# 8RelaySwitch.net
KiCad netlist of a schematic drawn in EAGLE
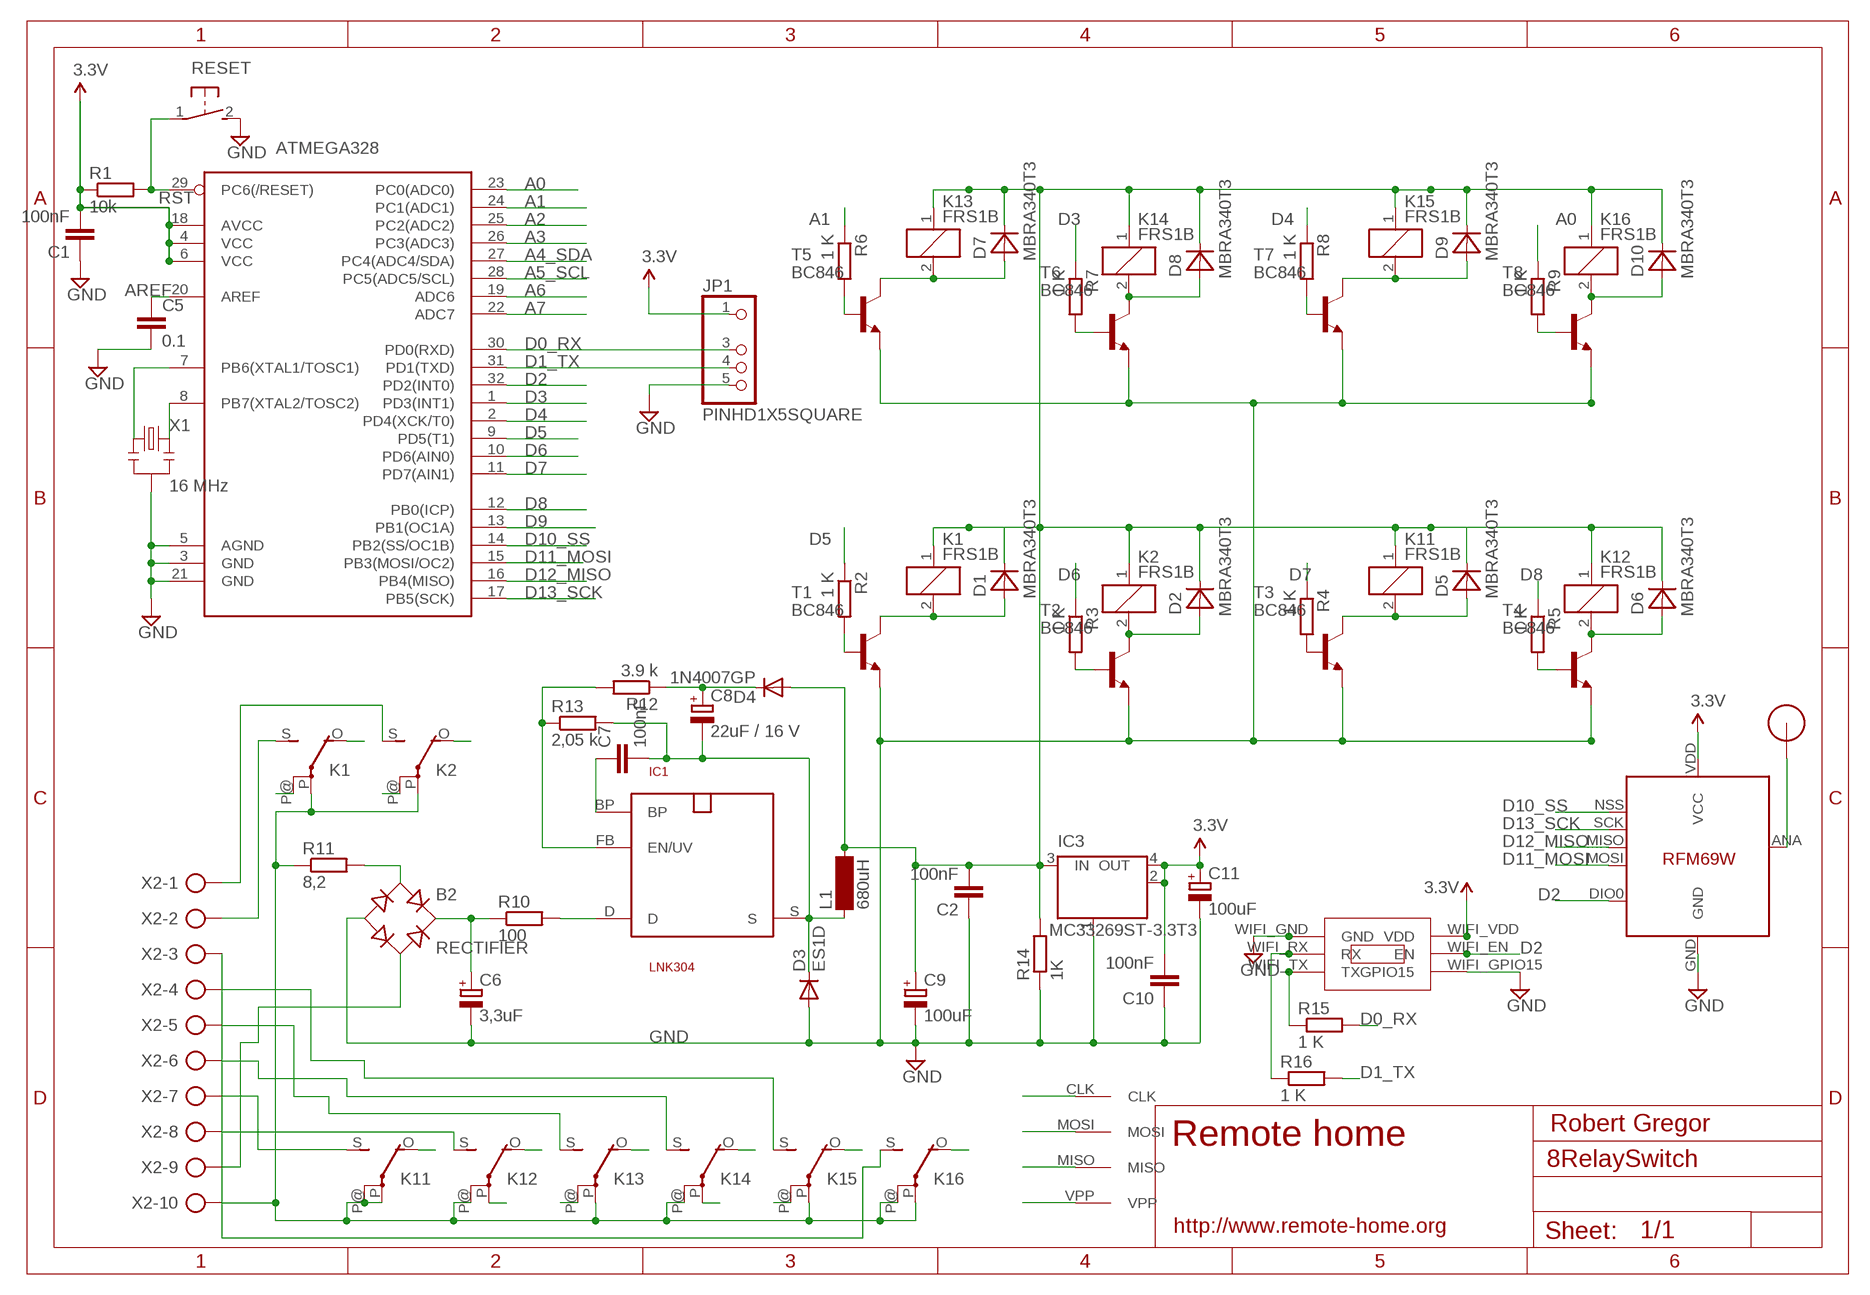
[diagram p0: schematic, sheet 1]

(export (version "E")
  (design (tool "Eeschema 10.0.6"))
  (components
    (comp (ref "ATMEGA328")
      (value "ATMega-328")
      (footprint "eagle-import:TQFP32-08")
      (libsource (lib "eagle-import") (part "ATMEGA168/328TQFP32"))
    )
    (comp (ref "B2")
      (value "RECTIFIER")
      (footprint "eagle-import:TO-269AA")
      (libsource (lib "eagle-import") (part "RECTIFIER-S40"))
    )
    (comp (ref "C1")
      (value "100nF")
      (footprint "eagle-import:C2012")
      (libsource (lib "eagle-import") (part "C-EUC2012"))
    )
    (comp (ref "C2")
      (value "100nF")
      (footprint "eagle-import:C2012")
      (libsource (lib "eagle-import") (part "C-EUC2012"))
    )
    (comp (ref "C5")
      (value "0.1")
      (footprint "eagle-import:C2012")
      (libsource (lib "eagle-import") (part "C-EUC2012"))
    )
    (comp (ref "C6")
      (value "3,3uF")
      (footprint "eagle-import:E5-10,5")
      (libsource (lib "eagle-import") (part "CPOL-EUE5-10.5"))
    )
    (comp (ref "C7")
      (value "100nF")
      (footprint "eagle-import:C2012")
      (libsource (lib "eagle-import") (part "C-EUC2012"))
    )
    (comp (ref "C8")
      (value "22uF / 16 V")
      (footprint "eagle-import:SMC_C")
      (libsource (lib "eagle-import") (part "CPOL-EUSMCC"))
    )
    (comp (ref "C9")
      (value "100uF")
      (footprint "eagle-import:SMC_B")
      (libsource (lib "eagle-import") (part "CPOL-EUSMCB"))
    )
    (comp (ref "C10")
      (value "100nF")
      (footprint "eagle-import:C2012")
      (libsource (lib "eagle-import") (part "C-EUC2012"))
    )
    (comp (ref "C11")
      (value "100uF")
      (footprint "eagle-import:SMC_B")
      (libsource (lib "eagle-import") (part "CPOL-EUSMCB"))
    )
    (comp (ref "D1")
      (value "MBRA340T3")
      (footprint "eagle-import:SMA")
      (libsource (lib "eagle-import") (part "MBRA340T3"))
    )
    (comp (ref "D2")
      (value "MBRA340T3")
      (footprint "eagle-import:SMA")
      (libsource (lib "eagle-import") (part "MBRA340T3"))
    )
    (comp (ref "D3")
      (value "ES1D")
      (footprint "eagle-import:DO214AC")
      (libsource (lib "eagle-import") (part "DIODE-DO214AC"))
    )
    (comp (ref "D4")
      (value "1N4007GP")
      (footprint "eagle-import:DO214AA")
      (libsource (lib "eagle-import") (part "DIODE-DO214AA"))
    )
    (comp (ref "D5")
      (value "MBRA340T3")
      (footprint "eagle-import:SMA")
      (libsource (lib "eagle-import") (part "MBRA340T3"))
    )
    (comp (ref "D6")
      (value "MBRA340T3")
      (footprint "eagle-import:SMA")
      (libsource (lib "eagle-import") (part "MBRA340T3"))
    )
    (comp (ref "D7")
      (value "MBRA340T3")
      (footprint "eagle-import:SMA")
      (libsource (lib "eagle-import") (part "MBRA340T3"))
    )
    (comp (ref "D8")
      (value "MBRA340T3")
      (footprint "eagle-import:SMA")
      (libsource (lib "eagle-import") (part "MBRA340T3"))
    )
    (comp (ref "D9")
      (value "MBRA340T3")
      (footprint "eagle-import:SMA")
      (libsource (lib "eagle-import") (part "MBRA340T3"))
    )
    (comp (ref "D10")
      (value "MBRA340T3")
      (footprint "eagle-import:SMA")
      (libsource (lib "eagle-import") (part "MBRA340T3"))
    )
    (comp (ref "IC1")
      (value "LNK304")
      (footprint "eagle-import:SO-8C")
      (libsource (lib "eagle-import") (part "SO-8C"))
    )
    (comp (ref "IC3")
      (value "MC33269ST-3.3T3")
      (footprint "eagle-import:SOT223")
      (libsource (lib "eagle-import") (part "MC33269ST-3.3T3"))
    )
    (comp (ref "JP1")
      (value "PINHD1X5SQUARE")
      (footprint "eagle-import:PINHD1X05-SQUARE")
      (libsource (lib "eagle-import") (part "PINHD1X5SQUARE"))
    )
    (comp (ref "K1")
      (value "FRS1B")
      (footprint "eagle-import:FRS1B")
      (libsource (lib "eagle-import") (part "FRS1B"))
    )
    (comp (ref "K2")
      (value "FRS1B")
      (footprint "eagle-import:FRS1B")
      (libsource (lib "eagle-import") (part "FRS1B"))
    )
    (comp (ref "K11")
      (value "FRS1B")
      (footprint "eagle-import:FRS1B")
      (libsource (lib "eagle-import") (part "FRS1B"))
    )
    (comp (ref "K12")
      (value "FRS1B")
      (footprint "eagle-import:FRS1B")
      (libsource (lib "eagle-import") (part "FRS1B"))
    )
    (comp (ref "K13")
      (value "FRS1B")
      (footprint "eagle-import:FRS1B")
      (libsource (lib "eagle-import") (part "FRS1B"))
    )
    (comp (ref "K14")
      (value "FRS1B")
      (footprint "eagle-import:FRS1B")
      (libsource (lib "eagle-import") (part "FRS1B"))
    )
    (comp (ref "K15")
      (value "FRS1B")
      (footprint "eagle-import:FRS1B")
      (libsource (lib "eagle-import") (part "FRS1B"))
    )
    (comp (ref "K16")
      (value "FRS1B")
      (footprint "eagle-import:FRS1B")
      (libsource (lib "eagle-import") (part "FRS1B"))
    )
    (comp (ref "L1")
      (value "680uH")
      (footprint "eagle-import:SD8")
      (libsource (lib "eagle-import") (part "SD8"))
    )
    (comp (ref "R1")
      (value "10k")
      (footprint "eagle-import:R2012")
      (libsource (lib "eagle-import") (part "R-EU_R2012"))
    )
    (comp (ref "R2")
      (value "1 K")
      (footprint "eagle-import:M2012")
      (libsource (lib "eagle-import") (part "R-EU_M2012"))
    )
    (comp (ref "R3")
      (value "1 K")
      (footprint "eagle-import:M2012")
      (libsource (lib "eagle-import") (part "R-EU_M2012"))
    )
    (comp (ref "R4")
      (value "1 K")
      (footprint "eagle-import:M2012")
      (libsource (lib "eagle-import") (part "R-EU_M2012"))
    )
    (comp (ref "R5")
      (value "1 K")
      (footprint "eagle-import:M2012")
      (libsource (lib "eagle-import") (part "R-EU_M2012"))
    )
    (comp (ref "R6")
      (value "1 K")
      (footprint "eagle-import:M2012")
      (libsource (lib "eagle-import") (part "R-EU_M2012"))
    )
    (comp (ref "R7")
      (value "1 K")
      (footprint "eagle-import:M2012")
      (libsource (lib "eagle-import") (part "R-EU_M2012"))
    )
    (comp (ref "R8")
      (value "1 K")
      (footprint "eagle-import:M2012")
      (libsource (lib "eagle-import") (part "R-EU_M2012"))
    )
    (comp (ref "R9")
      (value "1 K")
      (footprint "eagle-import:M2012")
      (libsource (lib "eagle-import") (part "R-EU_M2012"))
    )
    (comp (ref "R10")
      (value "100")
      (footprint "eagle-import:R2512W")
      (libsource (lib "eagle-import") (part "R-EU_R2512W"))
    )
    (comp (ref "R11")
      (value "8,2")
      (footprint "eagle-import:0411_12")
      (libsource (lib "eagle-import") (part "R-EU_0411/12"))
    )
    (comp (ref "R12")
      (value "3.9 k")
      (footprint "eagle-import:M2012")
      (libsource (lib "eagle-import") (part "R-EU_M2012"))
    )
    (comp (ref "R13")
      (value "2,05 k")
      (footprint "eagle-import:M2012")
      (libsource (lib "eagle-import") (part "R-EU_M2012"))
    )
    (comp (ref "R14")
      (value "1K")
      (footprint "eagle-import:M2012")
      (libsource (lib "eagle-import") (part "R-EU_M2012"))
    )
    (comp (ref "R15")
      (value "1 K")
      (footprint "eagle-import:M2012")
      (libsource (lib "eagle-import") (part "R-EU_M2012"))
    )
    (comp (ref "R16")
      (value "1 K")
      (footprint "eagle-import:M2012")
      (libsource (lib "eagle-import") (part "R-EU_M2012"))
    )
    (comp (ref "RESET")
      (value "DTSM-3")
      (footprint "eagle-import:DTSM-3")
      (libsource (lib "eagle-import") (part "DTSM-3"))
    )
    (comp (ref "T1")
      (value "BC846")
      (footprint "eagle-import:SOT23")
      (libsource (lib "eagle-import") (part "BC846"))
    )
    (comp (ref "T2")
      (value "BC846")
      (footprint "eagle-import:SOT23")
      (libsource (lib "eagle-import") (part "BC846"))
    )
    (comp (ref "T3")
      (value "BC846")
      (footprint "eagle-import:SOT23")
      (libsource (lib "eagle-import") (part "BC846"))
    )
    (comp (ref "T4")
      (value "BC846")
      (footprint "eagle-import:SOT23")
      (libsource (lib "eagle-import") (part "BC846"))
    )
    (comp (ref "T5")
      (value "BC846")
      (footprint "eagle-import:SOT23")
      (libsource (lib "eagle-import") (part "BC846"))
    )
    (comp (ref "T6")
      (value "BC846")
      (footprint "eagle-import:SOT23")
      (libsource (lib "eagle-import") (part "BC846"))
    )
    (comp (ref "T7")
      (value "BC846")
      (footprint "eagle-import:SOT23")
      (libsource (lib "eagle-import") (part "BC846"))
    )
    (comp (ref "T8")
      (value "BC846")
      (footprint "eagle-import:SOT23")
      (libsource (lib "eagle-import") (part "BC846"))
    )
    (comp (ref "U$1")
      (value "RFM12B_ANTENNA")
      (footprint "eagle-import:RFM12B-ANTENNA")
      (libsource (lib "eagle-import") (part "RFM12B_ANTENNA"))
    )
    (comp (ref "U$2")
      (value "AVRHEADERDIP")
      (footprint "eagle-import:AVRHEADER")
      (libsource (lib "eagle-import") (part "AVRHEADERDIP"))
    )
    (comp (ref "U$3")
      (value "ESP03")
      (footprint "eagle-import:ESP03")
      (libsource (lib "eagle-import") (part "ESP03"))
    )
    (comp (ref "U$5")
      (value "RFM69")
      (footprint "eagle-import:RFM69W-MINPADS")
      (libsource (lib "eagle-import") (part "RFM69"))
    )
    (comp (ref "X1")
      (value "16 MHz")
      (footprint "eagle-import:RESONATOR-SMD")
      (libsource (lib "eagle-import") (part "RESONATORSMD"))
    )
    (comp (ref "X2")
      (value "AK500/10")
      (footprint "eagle-import:AK500_10")
      (libsource (lib "eagle-import") (part "AK500/10"))
    )
  )
  (nets
    (net (code "1") (name "/A0") (class "Default")
      (node (ref "ATMEGA328") (pin "23") (pinfunction "PC0(ADC0)_23") (pintype "bidirectional"))
      (node (ref "R9") (pin "1") (pinfunction "1_1") (pintype "passive"))
    )
    (net (code "2") (name "/A1") (class "Default")
      (node (ref "ATMEGA328") (pin "24") (pinfunction "PC1(ADC1)_24") (pintype "bidirectional"))
      (node (ref "R6") (pin "1") (pinfunction "1_1") (pintype "passive"))
    )
    (net (code "3") (name "/A2") (class "Default")
      (node (ref "ATMEGA328") (pin "25") (pinfunction "PC2(ADC2)_25") (pintype "bidirectional"))
    )
    (net (code "4") (name "/A3") (class "Default")
      (node (ref "ATMEGA328") (pin "26") (pinfunction "PC3(ADC3)_26") (pintype "bidirectional"))
    )
    (net (code "5") (name "/A4_SDA") (class "Default")
      (node (ref "ATMEGA328") (pin "27") (pinfunction "PC4(ADC4/SDA)_27") (pintype "bidirectional"))
    )
    (net (code "6") (name "/A5_SCL") (class "Default")
      (node (ref "ATMEGA328") (pin "28") (pinfunction "PC5(ADC5/SCL)_28") (pintype "bidirectional"))
    )
    (net (code "7") (name "/A6") (class "Default")
      (node (ref "ATMEGA328") (pin "19") (pinfunction "ADC6_19") (pintype "bidirectional"))
    )
    (net (code "8") (name "/A7") (class "Default")
      (node (ref "ATMEGA328") (pin "22") (pinfunction "ADC7_22") (pintype "bidirectional"))
    )
    (net (code "9") (name "/AREF") (class "Default")
      (node (ref "ATMEGA328") (pin "20") (pinfunction "AREF_20") (pintype "bidirectional"))
      (node (ref "C5") (pin "1") (pinfunction "1_1") (pintype "passive"))
    )
    (net (code "10") (name "/D0_RX") (class "Default")
      (node (ref "ATMEGA328") (pin "30") (pinfunction "PD0(RXD)_30") (pintype "bidirectional"))
      (node (ref "JP1") (pin "3") (pinfunction "3_3") (pintype "passive"))
      (node (ref "R15") (pin "2") (pinfunction "2_2") (pintype "passive"))
    )
    (net (code "11") (name "/D1_TX") (class "Default")
      (node (ref "ATMEGA328") (pin "31") (pinfunction "PD1(TXD)_31") (pintype "bidirectional"))
      (node (ref "JP1") (pin "4") (pinfunction "4_4") (pintype "passive"))
      (node (ref "R16") (pin "2") (pinfunction "2_2") (pintype "passive"))
    )
    (net (code "12") (name "/D2") (class "Default")
      (node (ref "ATMEGA328") (pin "32") (pinfunction "PD2(INT0)_32") (pintype "bidirectional"))
      (node (ref "U$3") (pin "WIFI_EN") (pinfunction "EN_WIFI_EN") (pintype "input"))
      (node (ref "U$5") (pin "DIO0") (pinfunction "DIO0_DIO0") (pintype "open_collector"))
    )
    (net (code "13") (name "/D3") (class "Default")
      (node (ref "ATMEGA328") (pin "1") (pinfunction "PD3(INT1)_1") (pintype "bidirectional"))
      (node (ref "R7") (pin "1") (pinfunction "1_1") (pintype "passive"))
    )
    (net (code "14") (name "/D4") (class "Default")
      (node (ref "ATMEGA328") (pin "2") (pinfunction "PD4(XCK/T0)_2") (pintype "bidirectional"))
      (node (ref "R8") (pin "1") (pinfunction "1_1") (pintype "passive"))
    )
    (net (code "15") (name "/D5") (class "Default")
      (node (ref "ATMEGA328") (pin "9") (pinfunction "PD5(T1)_9") (pintype "bidirectional"))
      (node (ref "R2") (pin "1") (pinfunction "1_1") (pintype "passive"))
    )
    (net (code "16") (name "/D6") (class "Default")
      (node (ref "ATMEGA328") (pin "10") (pinfunction "PD6(AIN0)_10") (pintype "bidirectional"))
      (node (ref "R3") (pin "1") (pinfunction "1_1") (pintype "passive"))
    )
    (net (code "17") (name "/D7") (class "Default")
      (node (ref "ATMEGA328") (pin "11") (pinfunction "PD7(AIN1)_11") (pintype "bidirectional"))
      (node (ref "R4") (pin "1") (pinfunction "1_1") (pintype "passive"))
    )
    (net (code "18") (name "/D8") (class "Default")
      (node (ref "ATMEGA328") (pin "12") (pinfunction "PB0(ICP)_12") (pintype "bidirectional"))
      (node (ref "R5") (pin "1") (pinfunction "1_1") (pintype "passive"))
    )
    (net (code "19") (name "/D9") (class "Default")
      (node (ref "ATMEGA328") (pin "13") (pinfunction "PB1(OC1A)_13") (pintype "bidirectional"))
    )
    (net (code "20") (name "/D10_SS") (class "Default")
      (node (ref "ATMEGA328") (pin "14") (pinfunction "PB2(SS/OC1B)_14") (pintype "bidirectional"))
      (node (ref "U$5") (pin "NSS") (pinfunction "SEL_NSS") (pintype "input"))
    )
    (net (code "21") (name "/D11_MOSI") (class "Default")
      (node (ref "ATMEGA328") (pin "15") (pinfunction "PB3(MOSI/OC2)_15") (pintype "bidirectional"))
      (node (ref "U$2") (pin "MOSI") (pinfunction "MOSI_MOSI") (pintype "bidirectional"))
      (node (ref "U$5") (pin "MOSI") (pinfunction "MOSI_MOSI") (pintype "output"))
    )
    (net (code "22") (name "/D12_MISO") (class "Default")
      (node (ref "ATMEGA328") (pin "16") (pinfunction "PB4(MISO)_16") (pintype "bidirectional"))
      (node (ref "U$2") (pin "MISO") (pinfunction "MISO_MISO") (pintype "bidirectional"))
      (node (ref "U$5") (pin "MISO") (pinfunction "MISO_MISO") (pintype "input"))
    )
    (net (code "23") (name "/D13_SCK") (class "Default")
      (node (ref "ATMEGA328") (pin "17") (pinfunction "PB5(SCK)_17") (pintype "bidirectional"))
      (node (ref "U$2") (pin "CLK") (pinfunction "CLK_CLK") (pintype "bidirectional"))
      (node (ref "U$5") (pin "SCK") (pinfunction "SCK_SCK") (pintype "input"))
    )
    (net (code "24") (name "/RST") (class "Default")
      (node (ref "ATMEGA328") (pin "29") (pinfunction "PC6(/RESET)_29") (pintype "bidirectional"))
      (node (ref "R1") (pin "2") (pinfunction "2_2") (pintype "passive"))
      (node (ref "RESET") (pin "1") (pinfunction "1_1") (pintype "passive"))
      (node (ref "U$2") (pin "VPP") (pinfunction "VPP_VPP") (pintype "bidirectional"))
    )
    (net (code "25") (name "3.3V") (class "Default")
      (node (ref "ATMEGA328") (pin "18") (pinfunction "AVCC_18") (pintype "bidirectional"))
      (node (ref "ATMEGA328") (pin "4") (pinfunction "VCC_4") (pintype "bidirectional"))
      (node (ref "ATMEGA328") (pin "6") (pinfunction "VCC_6") (pintype "bidirectional"))
      (node (ref "C1") (pin "2") (pinfunction "2_2") (pintype "passive"))
      (node (ref "C10") (pin "2") (pinfunction "2_2") (pintype "passive"))
      (node (ref "C11") (pin "+") (pinfunction "+_+") (pintype "passive"))
      (node (ref "IC3") (pin "2") (pinfunction "OUT_2") (pintype "passive"))
      (node (ref "IC3") (pin "4") (pinfunction "OUT_4") (pintype "passive"))
      (node (ref "JP1") (pin "1") (pinfunction "1_1") (pintype "passive"))
      (node (ref "R1") (pin "1") (pinfunction "1_1") (pintype "passive"))
      (node (ref "U$3") (pin "WIFI_VDD") (pinfunction "VDD_WIFI_VDD") (pintype "power_in"))
      (node (ref "U$5") (pin "VDD") (pinfunction "VCC_VDD") (pintype "power_in"))
    )
    (net (code "26") (name "GND") (class "Default")
      (node (ref "ATMEGA328") (pin "21") (pinfunction "GND_21") (pintype "bidirectional"))
      (node (ref "ATMEGA328") (pin "3") (pinfunction "GND_3") (pintype "bidirectional"))
      (node (ref "ATMEGA328") (pin "5") (pinfunction "AGND_5") (pintype "bidirectional"))
      (node (ref "B2") (pin "-") (pinfunction "-_-") (pintype "passive"))
      (node (ref "C1") (pin "1") (pinfunction "1_1") (pintype "passive"))
      (node (ref "C10") (pin "1") (pinfunction "1_1") (pintype "passive"))
      (node (ref "C11") (pin "-") (pinfunction "-_-") (pintype "passive"))
      (node (ref "C2") (pin "1") (pinfunction "1_1") (pintype "passive"))
      (node (ref "C5") (pin "2") (pinfunction "2_2") (pintype "passive"))
      (node (ref "C6") (pin "-") (pinfunction "-_-") (pintype "passive"))
      (node (ref "C9") (pin "-") (pinfunction "-_-") (pintype "passive"))
      (node (ref "D3") (pin "A") (pinfunction "A_A") (pintype "passive"))
      (node (ref "IC3") (pin "1") (pinfunction "GND/ADJ_1") (pintype "input"))
      (node (ref "JP1") (pin "5") (pinfunction "5_5") (pintype "passive"))
      (node (ref "R14") (pin "1") (pinfunction "1_1") (pintype "passive"))
      (node (ref "RESET") (pin "2") (pinfunction "2_2") (pintype "passive"))
      (node (ref "T1") (pin "2") (pinfunction "E_2") (pintype "passive"))
      (node (ref "T2") (pin "2") (pinfunction "E_2") (pintype "passive"))
      (node (ref "T3") (pin "2") (pinfunction "E_2") (pintype "passive"))
      (node (ref "T4") (pin "2") (pinfunction "E_2") (pintype "passive"))
      (node (ref "T5") (pin "2") (pinfunction "E_2") (pintype "passive"))
      (node (ref "T6") (pin "2") (pinfunction "E_2") (pintype "passive"))
      (node (ref "T7") (pin "2") (pinfunction "E_2") (pintype "passive"))
      (node (ref "T8") (pin "2") (pinfunction "E_2") (pintype "passive"))
      (node (ref "U$3") (pin "WIFI_GND") (pinfunction "GND_WIFI_GND") (pintype "power_in"))
      (node (ref "U$3") (pin "WIFI_GPIO15") (pinfunction "GPIO15_WIFI_GPIO15") (pintype "input"))
      (node (ref "U$5") (pin "GND") (pinfunction "GND_GND") (pintype "power_in"))
      (node (ref "X1") (pin "2") (pinfunction "2_2") (pintype "passive"))
    )
    (net (code "27") (name "Net-(ATMEGA328-PB6(XTAL1{slash}TOSC1))") (class "Default")
      (node (ref "ATMEGA328") (pin "7") (pinfunction "PB6(XTAL1/TOSC1)_7") (pintype "bidirectional"))
      (node (ref "X1") (pin "1") (pinfunction "1_1") (pintype "passive"))
    )
    (net (code "28") (name "Net-(ATMEGA328-PB7(XTAL2{slash}TOSC2))") (class "Default")
      (node (ref "ATMEGA328") (pin "8") (pinfunction "PB7(XTAL2/TOSC2)_8") (pintype "bidirectional"))
      (node (ref "X1") (pin "3") (pinfunction "3_3") (pintype "passive"))
    )
    (net (code "29") (name "Net-(B2-Pad+)") (class "Default")
      (node (ref "B2") (pin "+") (pinfunction "+_+") (pintype "passive"))
      (node (ref "C6") (pin "+") (pinfunction "+_+") (pintype "passive"))
      (node (ref "R10") (pin "1") (pinfunction "1_1") (pintype "passive"))
    )
    (net (code "30") (name "Net-(B2-PadAC1)") (class "Default")
      (node (ref "B2") (pin "AC1") (pinfunction "AC1_AC1") (pintype "passive"))
      (node (ref "R11") (pin "2") (pinfunction "2_2") (pintype "passive"))
    )
    (net (code "31") (name "Net-(C7-Pad1)") (class "Default")
      (node (ref "C7") (pin "1") (pinfunction "1_1") (pintype "passive"))
      (node (ref "IC1") (pin "BP") (pinfunction "BP_BP") (pintype "passive"))
    )
    (net (code "32") (name "Net-(C7-Pad2)") (class "Default")
      (node (ref "C7") (pin "2") (pinfunction "2_2") (pintype "passive"))
      (node (ref "C8") (pin "-") (pinfunction "-_-") (pintype "passive"))
      (node (ref "D3") (pin "C") (pinfunction "C_C") (pintype "passive"))
      (node (ref "IC1") (pin "S") (pinfunction "S_S") (pintype "power_in"))
      (node (ref "L1") (pin "1") (pinfunction "1_1") (pintype "passive"))
      (node (ref "R13") (pin "2") (pinfunction "2_2") (pintype "passive"))
    )
    (net (code "33") (name "Net-(C8-Pad+)") (class "Default")
      (node (ref "C8") (pin "+") (pinfunction "+_+") (pintype "passive"))
      (node (ref "D4") (pin "C") (pinfunction "C_C") (pintype "passive"))
      (node (ref "R12") (pin "1") (pinfunction "1_1") (pintype "passive"))
    )
    (net (code "34") (name "Net-(IC1-EN{slash}UV)") (class "Default")
      (node (ref "IC1") (pin "FB") (pinfunction "EN/UV_FB") (pintype "input"))
      (node (ref "R12") (pin "2") (pinfunction "2_2") (pintype "passive"))
      (node (ref "R13") (pin "1") (pinfunction "1_1") (pintype "passive"))
    )
    (net (code "35") (name "Net-(IC1-PadD)") (class "Default")
      (node (ref "IC1") (pin "D") (pinfunction "D_D") (pintype "open_collector"))
      (node (ref "R10") (pin "2") (pinfunction "2_2") (pintype "passive"))
    )
    (net (code "36") (name "Net-(IC3-IN)") (class "Default")
      (node (ref "C2") (pin "2") (pinfunction "2_2") (pintype "passive"))
      (node (ref "C9") (pin "+") (pinfunction "+_+") (pintype "passive"))
      (node (ref "D1") (pin "C") (pinfunction "C_C") (pintype "passive"))
      (node (ref "D10") (pin "C") (pinfunction "C_C") (pintype "passive"))
      (node (ref "D2") (pin "C") (pinfunction "C_C") (pintype "passive"))
      (node (ref "D4") (pin "A") (pinfunction "A_A") (pintype "passive"))
      (node (ref "D5") (pin "C") (pinfunction "C_C") (pintype "passive"))
      (node (ref "D6") (pin "C") (pinfunction "C_C") (pintype "passive"))
      (node (ref "D7") (pin "C") (pinfunction "C_C") (pintype "passive"))
      (node (ref "D8") (pin "C") (pinfunction "C_C") (pintype "passive"))
      (node (ref "D9") (pin "C") (pinfunction "C_C") (pintype "passive"))
      (node (ref "IC3") (pin "3") (pinfunction "IN_3") (pintype "input"))
      (node (ref "K1") (pin "1") (pinfunction "1_1") (pintype "passive"))
      (node (ref "K11") (pin "1") (pinfunction "1_1") (pintype "passive"))
      (node (ref "K12") (pin "1") (pinfunction "1_1") (pintype "passive"))
      (node (ref "K13") (pin "1") (pinfunction "1_1") (pintype "passive"))
      (node (ref "K14") (pin "1") (pinfunction "1_1") (pintype "passive"))
      (node (ref "K15") (pin "1") (pinfunction "1_1") (pintype "passive"))
      (node (ref "K16") (pin "1") (pinfunction "1_1") (pintype "passive"))
      (node (ref "K2") (pin "1") (pinfunction "1_1") (pintype "passive"))
      (node (ref "L1") (pin "2") (pinfunction "2_2") (pintype "passive"))
      (node (ref "R14") (pin "2") (pinfunction "2_2") (pintype "passive"))
    )
    (net (code "37") (name "Net-(T1-B)") (class "Default")
      (node (ref "R2") (pin "2") (pinfunction "2_2") (pintype "passive"))
      (node (ref "T1") (pin "1") (pinfunction "B_1") (pintype "passive"))
    )
    (net (code "38") (name "Net-(T1-C)") (class "Default")
      (node (ref "D1") (pin "A") (pinfunction "A_A") (pintype "passive"))
      (node (ref "K1") (pin "2") (pinfunction "2_2") (pintype "passive"))
      (node (ref "T1") (pin "3") (pinfunction "C_3") (pintype "passive"))
    )
    (net (code "39") (name "Net-(T2-B)") (class "Default")
      (node (ref "R3") (pin "2") (pinfunction "2_2") (pintype "passive"))
      (node (ref "T2") (pin "1") (pinfunction "B_1") (pintype "passive"))
    )
    (net (code "40") (name "Net-(T2-C)") (class "Default")
      (node (ref "D2") (pin "A") (pinfunction "A_A") (pintype "passive"))
      (node (ref "K2") (pin "2") (pinfunction "2_2") (pintype "passive"))
      (node (ref "T2") (pin "3") (pinfunction "C_3") (pintype "passive"))
    )
    (net (code "41") (name "Net-(T3-B)") (class "Default")
      (node (ref "R4") (pin "2") (pinfunction "2_2") (pintype "passive"))
      (node (ref "T3") (pin "1") (pinfunction "B_1") (pintype "passive"))
    )
    (net (code "42") (name "Net-(T3-C)") (class "Default")
      (node (ref "D5") (pin "A") (pinfunction "A_A") (pintype "passive"))
      (node (ref "K11") (pin "2") (pinfunction "2_2") (pintype "passive"))
      (node (ref "T3") (pin "3") (pinfunction "C_3") (pintype "passive"))
    )
    (net (code "43") (name "Net-(T4-B)") (class "Default")
      (node (ref "R5") (pin "2") (pinfunction "2_2") (pintype "passive"))
      (node (ref "T4") (pin "1") (pinfunction "B_1") (pintype "passive"))
    )
    (net (code "44") (name "Net-(T4-C)") (class "Default")
      (node (ref "D6") (pin "A") (pinfunction "A_A") (pintype "passive"))
      (node (ref "K12") (pin "2") (pinfunction "2_2") (pintype "passive"))
      (node (ref "T4") (pin "3") (pinfunction "C_3") (pintype "passive"))
    )
    (net (code "45") (name "Net-(T5-B)") (class "Default")
      (node (ref "R6") (pin "2") (pinfunction "2_2") (pintype "passive"))
      (node (ref "T5") (pin "1") (pinfunction "B_1") (pintype "passive"))
    )
    (net (code "46") (name "Net-(T5-C)") (class "Default")
      (node (ref "D7") (pin "A") (pinfunction "A_A") (pintype "passive"))
      (node (ref "K13") (pin "2") (pinfunction "2_2") (pintype "passive"))
      (node (ref "T5") (pin "3") (pinfunction "C_3") (pintype "passive"))
    )
    (net (code "47") (name "Net-(T6-B)") (class "Default")
      (node (ref "R7") (pin "2") (pinfunction "2_2") (pintype "passive"))
      (node (ref "T6") (pin "1") (pinfunction "B_1") (pintype "passive"))
    )
    (net (code "48") (name "Net-(T6-C)") (class "Default")
      (node (ref "D8") (pin "A") (pinfunction "A_A") (pintype "passive"))
      (node (ref "K14") (pin "2") (pinfunction "2_2") (pintype "passive"))
      (node (ref "T6") (pin "3") (pinfunction "C_3") (pintype "passive"))
    )
    (net (code "49") (name "Net-(T7-B)") (class "Default")
      (node (ref "R8") (pin "2") (pinfunction "2_2") (pintype "passive"))
      (node (ref "T7") (pin "1") (pinfunction "B_1") (pintype "passive"))
    )
    (net (code "50") (name "Net-(T7-C)") (class "Default")
      (node (ref "D9") (pin "A") (pinfunction "A_A") (pintype "passive"))
      (node (ref "K15") (pin "2") (pinfunction "2_2") (pintype "passive"))
      (node (ref "T7") (pin "3") (pinfunction "C_3") (pintype "passive"))
    )
    (net (code "51") (name "Net-(T8-B)") (class "Default")
      (node (ref "R9") (pin "2") (pinfunction "2_2") (pintype "passive"))
      (node (ref "T8") (pin "1") (pinfunction "B_1") (pintype "passive"))
    )
    (net (code "52") (name "Net-(T8-C)") (class "Default")
      (node (ref "D10") (pin "A") (pinfunction "A_A") (pintype "passive"))
      (node (ref "K16") (pin "2") (pinfunction "2_2") (pintype "passive"))
      (node (ref "T8") (pin "3") (pinfunction "C_3") (pintype "passive"))
    )
    (net (code "53") (name "Net-(U$1-1)") (class "Default")
      (node (ref "U$1") (pin "P$1") (pinfunction "1_P$1") (pintype "bidirectional"))
      (node (ref "U$5") (pin "ANA") (pinfunction "ANT_ANA") (pintype "passive"))
    )
    (net (code "54") (name "Net-(U$3-RX)") (class "Default")
      (node (ref "R16") (pin "1") (pinfunction "1_1") (pintype "passive"))
      (node (ref "U$3") (pin "WIFI_RX") (pinfunction "RX_WIFI_RX") (pintype "input"))
    )
    (net (code "55") (name "Net-(U$3-TX)") (class "Default")
      (node (ref "R15") (pin "1") (pinfunction "1_1") (pintype "passive"))
      (node (ref "U$3") (pin "WIFI_TX") (pinfunction "TX_WIFI_TX") (pintype "output"))
    )
    (net (code "56") (name "Net-(X2A-KL)") (class "Default")
      (node (ref "K2") (pin "S") (pinfunction "S_S") (pintype "passive"))
      (node (ref "X2") (pin "1") (pinfunction "KL_1") (pintype "passive"))
    )
    (net (code "57") (name "Net-(X2B-KL)") (class "Default")
      (node (ref "K1") (pin "P") (pinfunction "P_P") (pintype "passive"))
      (node (ref "K11") (pin "P") (pinfunction "P_P") (pintype "passive"))
      (node (ref "K11") (pin "P@") (pinfunction "P_P@") (pintype "passive"))
      (node (ref "K12") (pin "P@") (pinfunction "P_P@") (pintype "passive"))
      (node (ref "K13") (pin "P") (pinfunction "P_P") (pintype "passive"))
      (node (ref "K14") (pin "P@") (pinfunction "P_P@") (pintype "passive"))
      (node (ref "K15") (pin "P") (pinfunction "P_P") (pintype "passive"))
      (node (ref "K16") (pin "P") (pinfunction "P_P") (pintype "passive"))
      (node (ref "K16") (pin "P@") (pinfunction "P_P@") (pintype "passive"))
      (node (ref "K2") (pin "P") (pinfunction "P_P") (pintype "passive"))
      (node (ref "R11") (pin "1") (pinfunction "1_1") (pintype "passive"))
      (node (ref "X2") (pin "10") (pinfunction "KL_10") (pintype "passive"))
    )
    (net (code "58") (name "Net-(X2C-KL)") (class "Default")
      (node (ref "K1") (pin "S") (pinfunction "S_S") (pintype "passive"))
      (node (ref "X2") (pin "2") (pinfunction "KL_2") (pintype "passive"))
    )
    (net (code "59") (name "Net-(X2D-KL)") (class "Default")
      (node (ref "K16") (pin "S") (pinfunction "S_S") (pintype "passive"))
      (node (ref "X2") (pin "3") (pinfunction "KL_3") (pintype "passive"))
    )
    (net (code "60") (name "Net-(X2E-KL)") (class "Default")
      (node (ref "K15") (pin "S") (pinfunction "S_S") (pintype "passive"))
      (node (ref "X2") (pin "4") (pinfunction "KL_4") (pintype "passive"))
    )
    (net (code "61") (name "Net-(X2F-KL)") (class "Default")
      (node (ref "K13") (pin "S") (pinfunction "S_S") (pintype "passive"))
      (node (ref "X2") (pin "5") (pinfunction "KL_5") (pintype "passive"))
    )
    (net (code "62") (name "Net-(X2G-KL)") (class "Default")
      (node (ref "K14") (pin "S") (pinfunction "S_S") (pintype "passive"))
      (node (ref "X2") (pin "6") (pinfunction "KL_6") (pintype "passive"))
    )
    (net (code "63") (name "Net-(X2H-KL)") (class "Default")
      (node (ref "K11") (pin "S") (pinfunction "S_S") (pintype "passive"))
      (node (ref "X2") (pin "7") (pinfunction "KL_7") (pintype "passive"))
    )
    (net (code "64") (name "Net-(X2I-KL)") (class "Default")
      (node (ref "K12") (pin "S") (pinfunction "S_S") (pintype "passive"))
      (node (ref "X2") (pin "8") (pinfunction "KL_8") (pintype "passive"))
    )
    (net (code "65") (name "Net-(X2J-KL)") (class "Default")
      (node (ref "B2") (pin "AC2") (pinfunction "AC2_AC2") (pintype "passive"))
      (node (ref "X2") (pin "9") (pinfunction "KL_9") (pintype "passive"))
    )
    (net (code "66") (name "unconnected-(K1-PadO)") (class "Default")
      (node (ref "K1") (pin "O") (pinfunction "O_O") (pintype "passive"))
    )
    (net (code "67") (name "unconnected-(K1B-P-PadP@)") (class "Default")
      (node (ref "K1") (pin "P@") (pinfunction "P_P@") (pintype "passive"))
    )
    (net (code "68") (name "unconnected-(K2-PadO)") (class "Default")
      (node (ref "K2") (pin "O") (pinfunction "O_O") (pintype "passive"))
    )
    (net (code "69") (name "unconnected-(K2B-P-PadP@)") (class "Default")
      (node (ref "K2") (pin "P@") (pinfunction "P_P@") (pintype "passive"))
    )
    (net (code "70") (name "unconnected-(K11-PadO)") (class "Default")
      (node (ref "K11") (pin "O") (pinfunction "O_O") (pintype "passive"))
    )
    (net (code "71") (name "unconnected-(K12-PadO)") (class "Default")
      (node (ref "K12") (pin "O") (pinfunction "O_O") (pintype "passive"))
    )
    (net (code "72") (name "unconnected-(K12-PadP)") (class "Default")
      (node (ref "K12") (pin "P") (pinfunction "P_P") (pintype "passive"))
    )
    (net (code "73") (name "unconnected-(K13-PadO)") (class "Default")
      (node (ref "K13") (pin "O") (pinfunction "O_O") (pintype "passive"))
    )
    (net (code "74") (name "unconnected-(K13B-P-PadP@)") (class "Default")
      (node (ref "K13") (pin "P@") (pinfunction "P_P@") (pintype "passive"))
    )
    (net (code "75") (name "unconnected-(K14-PadO)") (class "Default")
      (node (ref "K14") (pin "O") (pinfunction "O_O") (pintype "passive"))
    )
    (net (code "76") (name "unconnected-(K14-PadP)") (class "Default")
      (node (ref "K14") (pin "P") (pinfunction "P_P") (pintype "passive"))
    )
    (net (code "77") (name "unconnected-(K15-PadO)") (class "Default")
      (node (ref "K15") (pin "O") (pinfunction "O_O") (pintype "passive"))
    )
    (net (code "78") (name "unconnected-(K15B-P-PadP@)") (class "Default")
      (node (ref "K15") (pin "P@") (pinfunction "P_P@") (pintype "passive"))
    )
    (net (code "79") (name "unconnected-(K16-PadO)") (class "Default")
      (node (ref "K16") (pin "O") (pinfunction "O_O") (pintype "passive"))
    )
  )
)
